# raupino.net
KiCad netlist of a schematic drawn in EAGLE
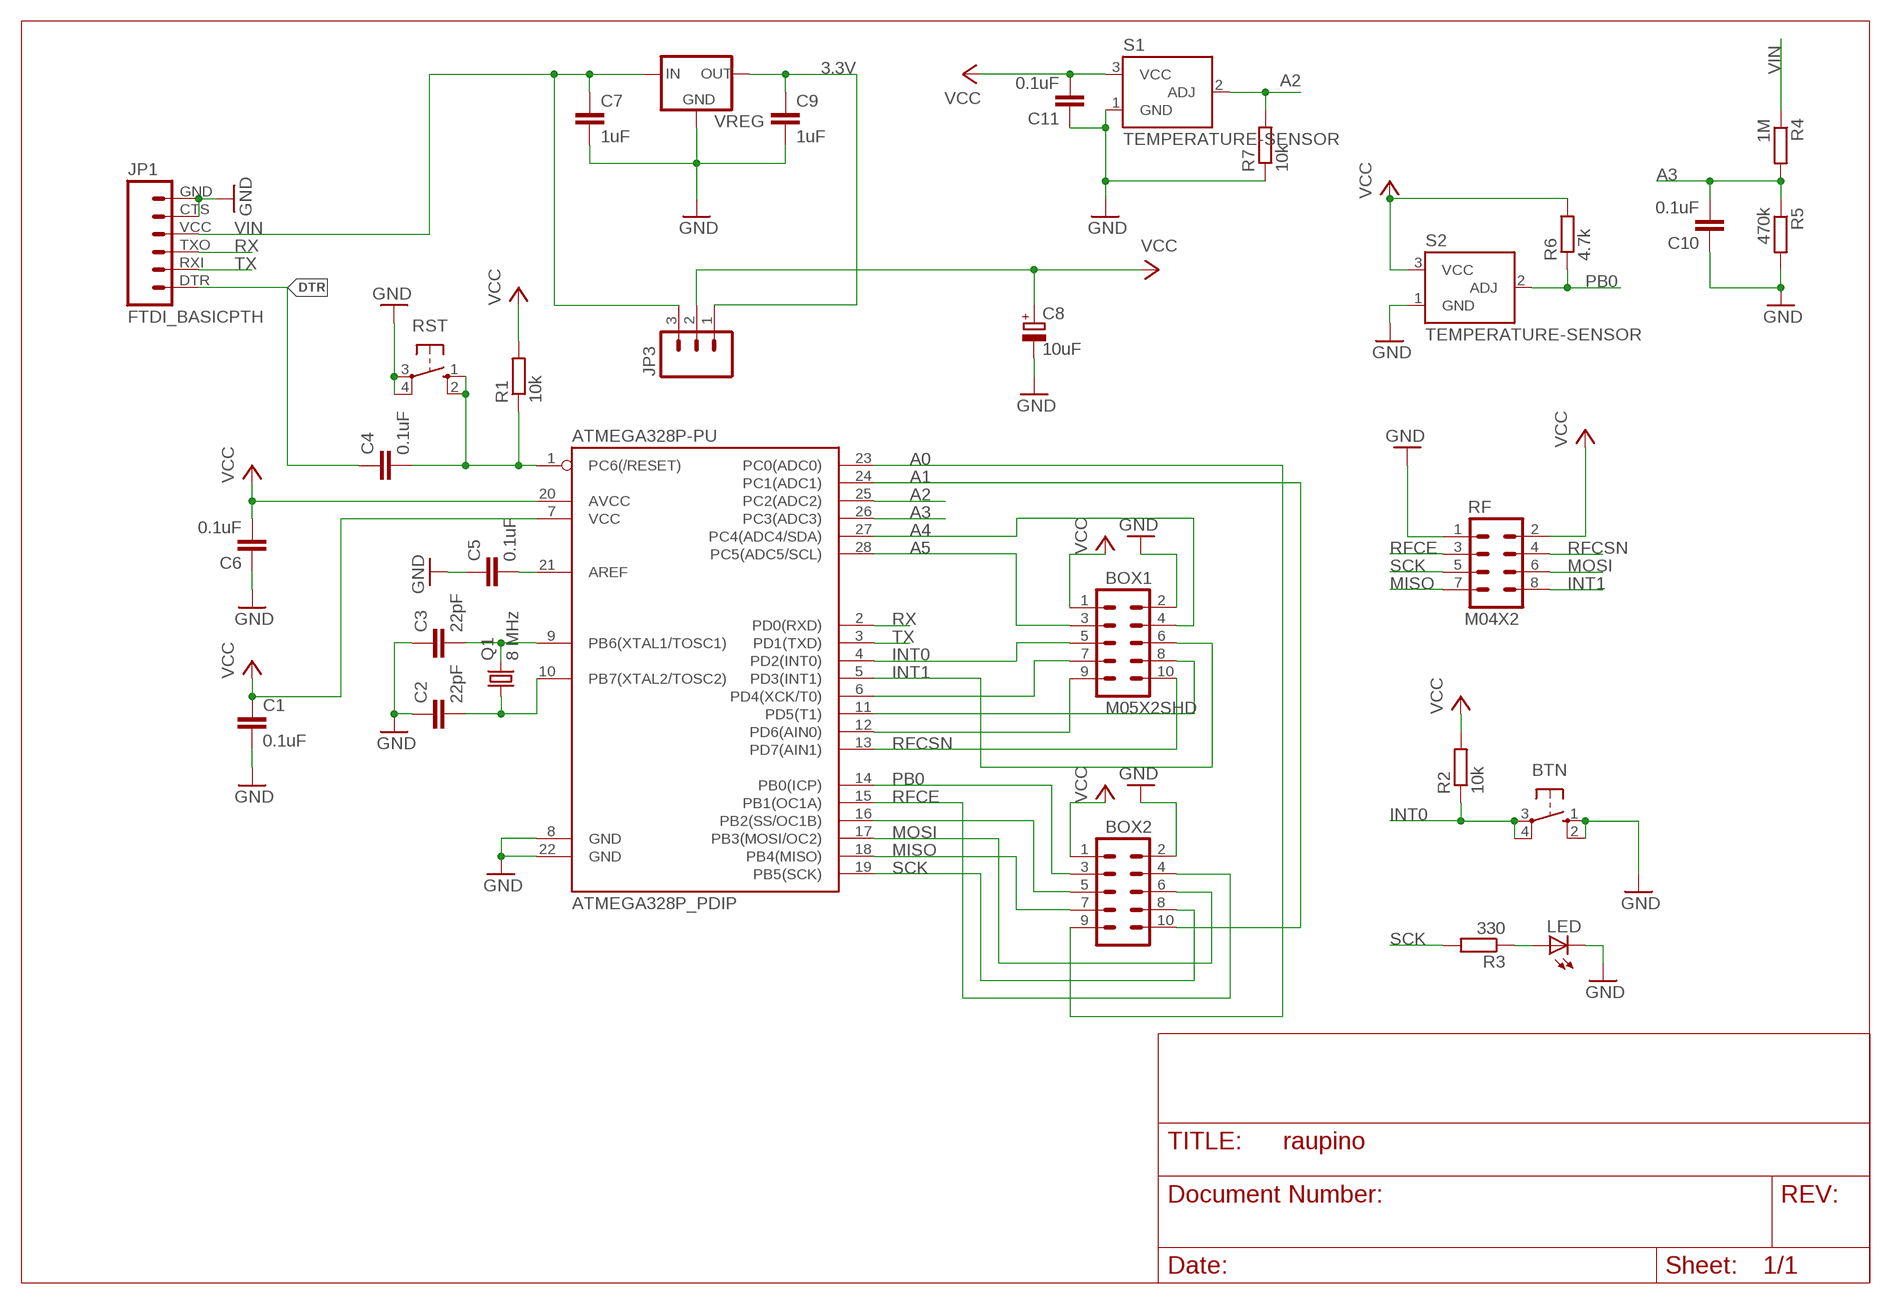
[diagram p0: schematic, sheet 1]

(export (version "E")
  (design (tool "Eeschema 10.0.6"))
  (components
    (comp (ref "ATMEGA328P-PU")
      (value "ATMEGA328P_PDIP")
      (footprint "eagle-import:DIL28-3")
      (libsource (lib "eagle-import") (part "ATMEGA328P_PDIP"))
    )
    (comp (ref "BOX1")
      (value "M05X2SHD")
      (footprint "eagle-import:2X5-SHROUDED")
      (libsource (lib "eagle-import") (part "M05X2SHD"))
    )
    (comp (ref "BOX2")
      (value "M05X2SHD")
      (footprint "eagle-import:2X5-SHROUDED")
      (libsource (lib "eagle-import") (part "M05X2SHD"))
    )
    (comp (ref "BTN")
      (value "10-XX")
      (footprint "eagle-import:B3F-10XX")
      (fields (field (name "MPN") "B3F-1000"))
      (libsource (lib "eagle-import") (part "10-XX"))
    )
    (comp (ref "C1")
      (value "0.1uF")
      (footprint "eagle-import:C0805")
      (libsource (lib "eagle-import") (part "C-EUC0805"))
    )
    (comp (ref "C2")
      (value "22pF")
      (footprint "eagle-import:C0805")
      (libsource (lib "eagle-import") (part "C-EUC0805"))
    )
    (comp (ref "C3")
      (value "22pF")
      (footprint "eagle-import:C0805")
      (libsource (lib "eagle-import") (part "C-EUC0805"))
    )
    (comp (ref "C4")
      (value "0.1uF")
      (footprint "eagle-import:C0805")
      (libsource (lib "eagle-import") (part "C-EUC0805"))
    )
    (comp (ref "C5")
      (value "0.1uF")
      (footprint "eagle-import:C0805")
      (libsource (lib "eagle-import") (part "C-EUC0805"))
    )
    (comp (ref "C6")
      (value "0.1uF")
      (footprint "eagle-import:C0805")
      (libsource (lib "eagle-import") (part "C-EUC0805"))
    )
    (comp (ref "C7")
      (value "1uF")
      (footprint "eagle-import:C050-025X075")
      (libsource (lib "eagle-import") (part "C-EU050-025X075"))
    )
    (comp (ref "C8")
      (value "10uF")
      (footprint "eagle-import:TT2D5L")
      (libsource (lib "eagle-import") (part "CPOL-EUTT2D5L"))
    )
    (comp (ref "C9")
      (value "1uF")
      (footprint "eagle-import:C050-025X075")
      (libsource (lib "eagle-import") (part "C-EU050-025X075"))
    )
    (comp (ref "C10")
      (value "0.1uF")
      (footprint "eagle-import:C0805")
      (libsource (lib "eagle-import") (part "C-EUC0805"))
    )
    (comp (ref "C11")
      (value "0.1uF")
      (footprint "eagle-import:C0805")
      (libsource (lib "eagle-import") (part "C-EUC0805"))
    )
    (comp (ref "JP1")
      (value "FTDI_BASICPTH")
      (footprint "eagle-import:FTDI_BASIC")
      (libsource (lib "eagle-import") (part "FTDI_BASICPTH"))
    )
    (comp (ref "JP3")
      (value "M03PTH")
      (footprint "eagle-import:1X03")
      (libsource (lib "eagle-import") (part "M03PTH"))
    )
    (comp (ref "LED")
      (value "LED3MM")
      (footprint "eagle-import:LED3MM")
      (libsource (lib "eagle-import") (part "LED3MM"))
    )
    (comp (ref "Q1")
      (value "8 MHz")
      (footprint "eagle-import:HC49US")
      (libsource (lib "eagle-import") (part "CRYSTALHC49US"))
    )
    (comp (ref "R1")
      (value "10k")
      (footprint "eagle-import:R0805")
      (libsource (lib "eagle-import") (part "R-EU_R0805"))
    )
    (comp (ref "R2")
      (value "10k")
      (footprint "eagle-import:R0805")
      (libsource (lib "eagle-import") (part "R-EU_R0805"))
    )
    (comp (ref "R3")
      (value "330")
      (footprint "eagle-import:R0805")
      (libsource (lib "eagle-import") (part "R-EU_R0805"))
    )
    (comp (ref "R4")
      (value "1M")
      (footprint "eagle-import:R0805")
      (libsource (lib "eagle-import") (part "R-EU_R0805"))
    )
    (comp (ref "R5")
      (value "470k")
      (footprint "eagle-import:R0805")
      (libsource (lib "eagle-import") (part "R-EU_R0805"))
    )
    (comp (ref "R6")
      (value "4.7k")
      (footprint "eagle-import:R0805")
      (libsource (lib "eagle-import") (part "R-EU_R0805"))
    )
    (comp (ref "R7")
      (value "10k")
      (footprint "eagle-import:R0805")
      (libsource (lib "eagle-import") (part "R-EU_R0805"))
    )
    (comp (ref "RF")
      (value "M04X2")
      (footprint "eagle-import:2X4")
      (libsource (lib "eagle-import") (part "M04X2"))
    )
    (comp (ref "RST")
      (value "10-XX")
      (footprint "eagle-import:B3F-10XX")
      (fields (field (name "MPN") "B3F-1000"))
      (libsource (lib "eagle-import") (part "10-XX"))
    )
    (comp (ref "S1")
      (value "TEMPERATURE-SENSOR")
      (footprint "eagle-import:TO-92")
      (libsource (lib "eagle-import") (part "TEMPERATURE-SENSOR"))
    )
    (comp (ref "S2")
      (value "TEMPERATURE-SENSOR")
      (footprint "eagle-import:TO-92")
      (libsource (lib "eagle-import") (part "TEMPERATURE-SENSOR"))
    )
    (comp (ref "VREG")
      (value "78LXX")
      (footprint "eagle-import:78LXX")
      (libsource (lib "eagle-import") (part "78LXX"))
    )
  )
  (nets
    (net (code "1") (name "/3.3V") (class "Default")
      (node (ref "C9") (pin "1") (pinfunction "1_1") (pintype "passive"))
      (node (ref "JP3") (pin "1") (pinfunction "1_1") (pintype "passive"))
      (node (ref "VREG") (pin "OUT") (pinfunction "OUT_OUT") (pintype "passive"))
    )
    (net (code "2") (name "/A0") (class "Default")
      (node (ref "ATMEGA328P-PU") (pin "23") (pinfunction "PC0(ADC0)_23") (pintype "bidirectional"))
      (node (ref "BOX2") (pin "9") (pinfunction "9_9") (pintype "passive"))
    )
    (net (code "3") (name "/A1") (class "Default")
      (node (ref "ATMEGA328P-PU") (pin "24") (pinfunction "PC1(ADC1)_24") (pintype "bidirectional"))
      (node (ref "BOX2") (pin "10") (pinfunction "10_10") (pintype "passive"))
    )
    (net (code "4") (name "/A2") (class "Default")
      (node (ref "ATMEGA328P-PU") (pin "25") (pinfunction "PC2(ADC2)_25") (pintype "bidirectional"))
      (node (ref "R7") (pin "2") (pinfunction "2_2") (pintype "passive"))
      (node (ref "S1") (pin "2") (pinfunction "ADJ_2") (pintype "bidirectional"))
    )
    (net (code "5") (name "/A3") (class "Default")
      (node (ref "ATMEGA328P-PU") (pin "26") (pinfunction "PC3(ADC3)_26") (pintype "bidirectional"))
      (node (ref "C10") (pin "2") (pinfunction "2_2") (pintype "passive"))
      (node (ref "R4") (pin "2") (pinfunction "2_2") (pintype "passive"))
      (node (ref "R5") (pin "1") (pinfunction "1_1") (pintype "passive"))
    )
    (net (code "6") (name "/A4") (class "Default")
      (node (ref "ATMEGA328P-PU") (pin "27") (pinfunction "PC4(ADC4/SDA)_27") (pintype "bidirectional"))
      (node (ref "BOX1") (pin "4") (pinfunction "4_4") (pintype "passive"))
    )
    (net (code "7") (name "/A5") (class "Default")
      (node (ref "ATMEGA328P-PU") (pin "28") (pinfunction "PC5(ADC5/SCL)_28") (pintype "bidirectional"))
      (node (ref "BOX1") (pin "3") (pinfunction "3_3") (pintype "passive"))
    )
    (net (code "8") (name "/INT0") (class "Default")
      (node (ref "ATMEGA328P-PU") (pin "4") (pinfunction "PD2(INT0)_4") (pintype "bidirectional"))
      (node (ref "BOX1") (pin "5") (pinfunction "5_5") (pintype "passive"))
      (node (ref "BTN") (pin "3") (pinfunction "P_3") (pintype "passive"))
      (node (ref "BTN") (pin "4") (pinfunction "P1_4") (pintype "passive"))
      (node (ref "R2") (pin "1") (pinfunction "1_1") (pintype "passive"))
    )
    (net (code "9") (name "/INT1") (class "Default")
      (node (ref "ATMEGA328P-PU") (pin "5") (pinfunction "PD3(INT1)_5") (pintype "bidirectional"))
      (node (ref "BOX1") (pin "6") (pinfunction "6_6") (pintype "passive"))
      (node (ref "RF") (pin "8") (pinfunction "8_8") (pintype "passive"))
    )
    (net (code "10") (name "/MISO") (class "Default")
      (node (ref "ATMEGA328P-PU") (pin "18") (pinfunction "PB4(MISO)_18") (pintype "bidirectional"))
      (node (ref "BOX2") (pin "7") (pinfunction "7_7") (pintype "passive"))
      (node (ref "RF") (pin "7") (pinfunction "7_7") (pintype "passive"))
    )
    (net (code "11") (name "/MOSI") (class "Default")
      (node (ref "ATMEGA328P-PU") (pin "17") (pinfunction "PB3(MOSI/OC2)_17") (pintype "bidirectional"))
      (node (ref "BOX2") (pin "6") (pinfunction "6_6") (pintype "passive"))
      (node (ref "RF") (pin "6") (pinfunction "6_6") (pintype "passive"))
    )
    (net (code "12") (name "/PB0") (class "Default")
      (node (ref "ATMEGA328P-PU") (pin "14") (pinfunction "PB0(ICP)_14") (pintype "bidirectional"))
      (node (ref "BOX2") (pin "3") (pinfunction "3_3") (pintype "passive"))
      (node (ref "R6") (pin "1") (pinfunction "1_1") (pintype "passive"))
      (node (ref "S2") (pin "2") (pinfunction "ADJ_2") (pintype "bidirectional"))
    )
    (net (code "13") (name "/RFCE") (class "Default")
      (node (ref "ATMEGA328P-PU") (pin "15") (pinfunction "PB1(OC1A)_15") (pintype "bidirectional"))
      (node (ref "BOX2") (pin "4") (pinfunction "4_4") (pintype "passive"))
      (node (ref "RF") (pin "3") (pinfunction "3_3") (pintype "passive"))
    )
    (net (code "14") (name "/RFCSN") (class "Default")
      (node (ref "ATMEGA328P-PU") (pin "13") (pinfunction "PD7(AIN1)_13") (pintype "bidirectional"))
      (node (ref "BOX1") (pin "10") (pinfunction "10_10") (pintype "passive"))
      (node (ref "RF") (pin "4") (pinfunction "4_4") (pintype "passive"))
    )
    (net (code "15") (name "/RX") (class "Default")
      (node (ref "ATMEGA328P-PU") (pin "2") (pinfunction "PD0(RXD)_2") (pintype "bidirectional"))
      (node (ref "JP1") (pin "TXO") (pinfunction "3_TXO") (pintype "passive"))
    )
    (net (code "16") (name "/SCK") (class "Default")
      (node (ref "ATMEGA328P-PU") (pin "19") (pinfunction "PB5(SCK)_19") (pintype "bidirectional"))
      (node (ref "BOX2") (pin "8") (pinfunction "8_8") (pintype "passive"))
      (node (ref "R3") (pin "2") (pinfunction "2_2") (pintype "passive"))
      (node (ref "RF") (pin "5") (pinfunction "5_5") (pintype "passive"))
    )
    (net (code "17") (name "/TX") (class "Default")
      (node (ref "ATMEGA328P-PU") (pin "3") (pinfunction "PD1(TXD)_3") (pintype "bidirectional"))
      (node (ref "JP1") (pin "RXI") (pinfunction "2_RXI") (pintype "passive"))
    )
    (net (code "18") (name "/VIN") (class "Default")
      (node (ref "C7") (pin "1") (pinfunction "1_1") (pintype "passive"))
      (node (ref "JP1") (pin "VCC") (pinfunction "4_VCC") (pintype "passive"))
      (node (ref "JP3") (pin "3") (pinfunction "3_3") (pintype "passive"))
      (node (ref "R4") (pin "1") (pinfunction "1_1") (pintype "passive"))
      (node (ref "VREG") (pin "IN") (pinfunction "IN_IN") (pintype "input"))
    )
    (net (code "19") (name "DTR") (class "Default")
      (node (ref "C4") (pin "1") (pinfunction "1_1") (pintype "passive"))
      (node (ref "JP1") (pin "DTR") (pinfunction "1_DTR") (pintype "passive"))
    )
    (net (code "20") (name "GND") (class "Default")
      (node (ref "ATMEGA328P-PU") (pin "22") (pinfunction "GND_22") (pintype "bidirectional"))
      (node (ref "ATMEGA328P-PU") (pin "8") (pinfunction "GND_8") (pintype "bidirectional"))
      (node (ref "BOX1") (pin "2") (pinfunction "2_2") (pintype "passive"))
      (node (ref "BOX2") (pin "2") (pinfunction "2_2") (pintype "passive"))
      (node (ref "BTN") (pin "1") (pinfunction "S_1") (pintype "passive"))
      (node (ref "BTN") (pin "2") (pinfunction "S1_2") (pintype "passive"))
      (node (ref "C1") (pin "2") (pinfunction "2_2") (pintype "passive"))
      (node (ref "C10") (pin "1") (pinfunction "1_1") (pintype "passive"))
      (node (ref "C11") (pin "1") (pinfunction "1_1") (pintype "passive"))
      (node (ref "C2") (pin "1") (pinfunction "1_1") (pintype "passive"))
      (node (ref "C3") (pin "1") (pinfunction "1_1") (pintype "passive"))
      (node (ref "C5") (pin "1") (pinfunction "1_1") (pintype "passive"))
      (node (ref "C6") (pin "1") (pinfunction "1_1") (pintype "passive"))
      (node (ref "C7") (pin "2") (pinfunction "2_2") (pintype "passive"))
      (node (ref "C8") (pin "-") (pinfunction "-_-") (pintype "passive"))
      (node (ref "C9") (pin "2") (pinfunction "2_2") (pintype "passive"))
      (node (ref "JP1") (pin "CTS") (pinfunction "5_CTS") (pintype "passive"))
      (node (ref "JP1") (pin "GND") (pinfunction "6_GND") (pintype "passive"))
      (node (ref "LED") (pin "K") (pinfunction "C_K") (pintype "passive"))
      (node (ref "R5") (pin "2") (pinfunction "2_2") (pintype "passive"))
      (node (ref "R7") (pin "1") (pinfunction "1_1") (pintype "passive"))
      (node (ref "RF") (pin "1") (pinfunction "1_1") (pintype "passive"))
      (node (ref "RST") (pin "3") (pinfunction "P_3") (pintype "passive"))
      (node (ref "RST") (pin "4") (pinfunction "P1_4") (pintype "passive"))
      (node (ref "S1") (pin "1") (pinfunction "GND_1") (pintype "bidirectional"))
      (node (ref "S2") (pin "1") (pinfunction "GND_1") (pintype "bidirectional"))
      (node (ref "VREG") (pin "GND") (pinfunction "GND_GND") (pintype "input"))
    )
    (net (code "21") (name "Net-(ATMEGA328P-PU-AREF)") (class "Default")
      (node (ref "ATMEGA328P-PU") (pin "21") (pinfunction "AREF_21") (pintype "bidirectional"))
      (node (ref "C5") (pin "2") (pinfunction "2_2") (pintype "passive"))
    )
    (net (code "22") (name "Net-(ATMEGA328P-PU-PB2(SS{slash}OC1B))") (class "Default")
      (node (ref "ATMEGA328P-PU") (pin "16") (pinfunction "PB2(SS/OC1B)_16") (pintype "bidirectional"))
      (node (ref "BOX2") (pin "5") (pinfunction "5_5") (pintype "passive"))
    )
    (net (code "23") (name "Net-(ATMEGA328P-PU-PB6(XTAL1{slash}TOSC1))") (class "Default")
      (node (ref "ATMEGA328P-PU") (pin "9") (pinfunction "PB6(XTAL1/TOSC1)_9") (pintype "bidirectional"))
      (node (ref "C3") (pin "2") (pinfunction "2_2") (pintype "passive"))
      (node (ref "Q1") (pin "2") (pinfunction "2_2") (pintype "passive"))
    )
    (net (code "24") (name "Net-(ATMEGA328P-PU-PB7(XTAL2{slash}TOSC2))") (class "Default")
      (node (ref "ATMEGA328P-PU") (pin "10") (pinfunction "PB7(XTAL2/TOSC2)_10") (pintype "bidirectional"))
      (node (ref "C2") (pin "2") (pinfunction "2_2") (pintype "passive"))
      (node (ref "Q1") (pin "1") (pinfunction "1_1") (pintype "passive"))
    )
    (net (code "25") (name "Net-(ATMEGA328P-PU-PC6({slash}RESET))") (class "Default")
      (node (ref "ATMEGA328P-PU") (pin "1") (pinfunction "PC6(/RESET)_1") (pintype "bidirectional"))
      (node (ref "C4") (pin "2") (pinfunction "2_2") (pintype "passive"))
      (node (ref "R1") (pin "1") (pinfunction "1_1") (pintype "passive"))
      (node (ref "RST") (pin "1") (pinfunction "S_1") (pintype "passive"))
      (node (ref "RST") (pin "2") (pinfunction "S1_2") (pintype "passive"))
    )
    (net (code "26") (name "Net-(ATMEGA328P-PU-PD4(XCK{slash}T0))") (class "Default")
      (node (ref "ATMEGA328P-PU") (pin "6") (pinfunction "PD4(XCK/T0)_6") (pintype "bidirectional"))
      (node (ref "BOX1") (pin "7") (pinfunction "7_7") (pintype "passive"))
    )
    (net (code "27") (name "Net-(ATMEGA328P-PU-PD5(T1))") (class "Default")
      (node (ref "ATMEGA328P-PU") (pin "11") (pinfunction "PD5(T1)_11") (pintype "bidirectional"))
      (node (ref "BOX1") (pin "8") (pinfunction "8_8") (pintype "passive"))
    )
    (net (code "28") (name "Net-(ATMEGA328P-PU-PD6(AIN0))") (class "Default")
      (node (ref "ATMEGA328P-PU") (pin "12") (pinfunction "PD6(AIN0)_12") (pintype "bidirectional"))
      (node (ref "BOX1") (pin "9") (pinfunction "9_9") (pintype "passive"))
    )
    (net (code "29") (name "Net-(LED-PadA)") (class "Default")
      (node (ref "LED") (pin "A") (pinfunction "A_A") (pintype "passive"))
      (node (ref "R3") (pin "1") (pinfunction "1_1") (pintype "passive"))
    )
    (net (code "30") (name "VCC") (class "Default")
      (node (ref "ATMEGA328P-PU") (pin "20") (pinfunction "AVCC_20") (pintype "bidirectional"))
      (node (ref "ATMEGA328P-PU") (pin "7") (pinfunction "VCC_7") (pintype "bidirectional"))
      (node (ref "BOX1") (pin "1") (pinfunction "1_1") (pintype "passive"))
      (node (ref "BOX2") (pin "1") (pinfunction "1_1") (pintype "passive"))
      (node (ref "C1") (pin "1") (pinfunction "1_1") (pintype "passive"))
      (node (ref "C11") (pin "2") (pinfunction "2_2") (pintype "passive"))
      (node (ref "C6") (pin "2") (pinfunction "2_2") (pintype "passive"))
      (node (ref "C8") (pin "+") (pinfunction "+_+") (pintype "passive"))
      (node (ref "JP3") (pin "2") (pinfunction "2_2") (pintype "passive"))
      (node (ref "R1") (pin "2") (pinfunction "2_2") (pintype "passive"))
      (node (ref "R2") (pin "2") (pinfunction "2_2") (pintype "passive"))
      (node (ref "R6") (pin "2") (pinfunction "2_2") (pintype "passive"))
      (node (ref "RF") (pin "2") (pinfunction "2_2") (pintype "passive"))
      (node (ref "S1") (pin "3") (pinfunction "VCC_3") (pintype "bidirectional"))
      (node (ref "S2") (pin "3") (pinfunction "VCC_3") (pintype "bidirectional"))
    )
  )
)
